# shinobi_BLE_Rev010001.net
KiCad netlist of a schematic drawn in EAGLE
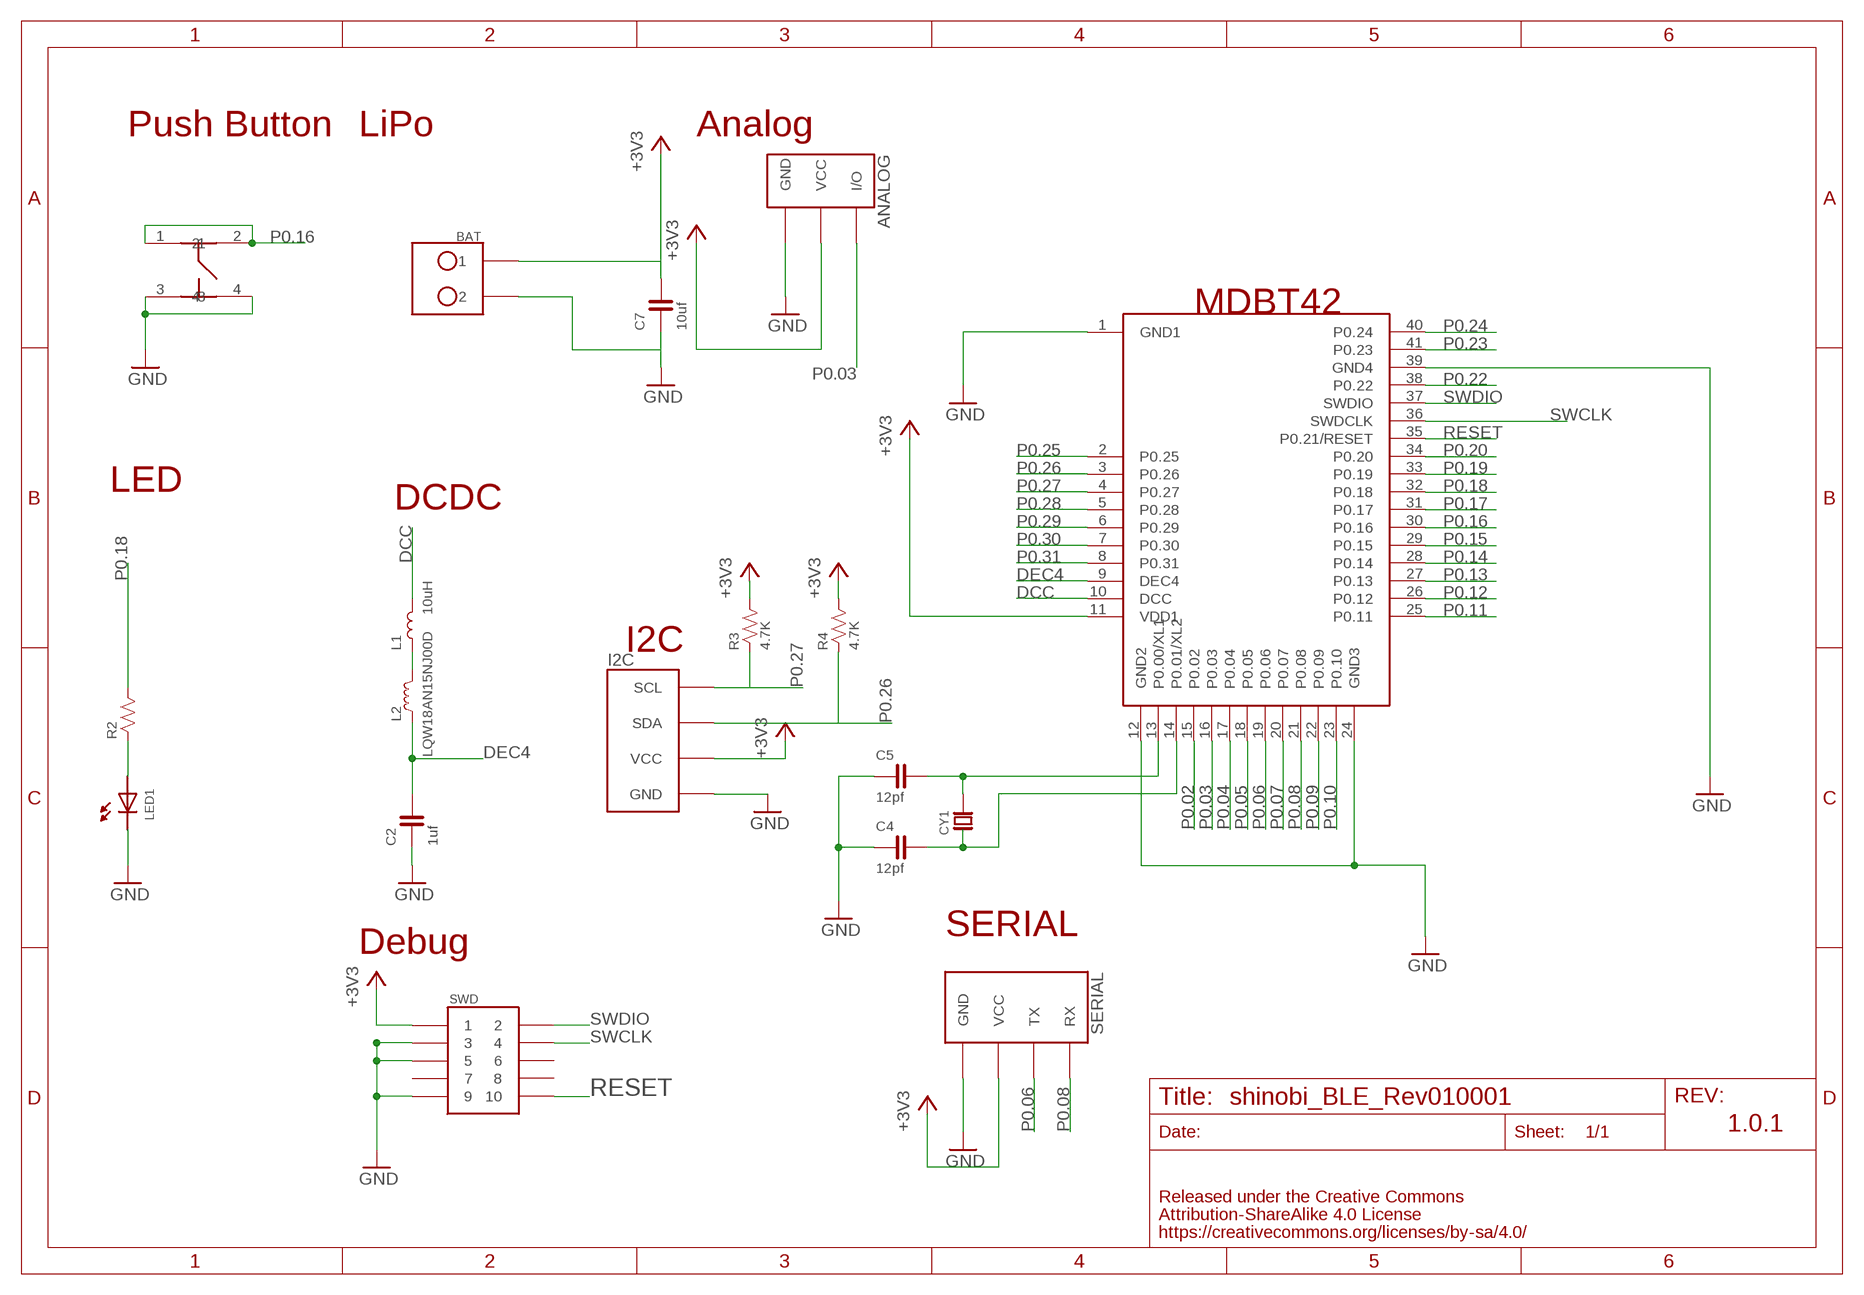
[diagram p0: schematic, sheet 1]

(export (version "E")
  (design (tool "Eeschema 10.0.6"))
  (components
    (comp (ref "ANALOG")
      (value "FABO_BRICK_3PIN-S03B-PASK-2_LONG")
      (footprint "eagle-import:FABO_BRICK_3PIN_S03B-PASK-2_LONG")
      (libsource (lib "eagle-import") (part "FABO_BRICK_3PIN-S03B-PASK-2_LONG"))
    )
    (comp (ref "BAT")
      (value "S2B-PH-SM4_TB")
      (footprint "eagle-import:S2B-PH-SM4-TB")
      (libsource (lib "eagle-import") (part "S2B-PH-SM4_TB"))
    )
    (comp (ref "C2")
      (value "1uf")
      (footprint "eagle-import:0603")
      (libsource (lib "eagle-import") (part "CAPACITOR-0603"))
    )
    (comp (ref "C4")
      (value "12pf")
      (footprint "eagle-import:0603")
      (libsource (lib "eagle-import") (part "CAPACITOR-0603"))
    )
    (comp (ref "C5")
      (value "12pf")
      (footprint "eagle-import:0603")
      (libsource (lib "eagle-import") (part "CAPACITOR-0603"))
    )
    (comp (ref "C7")
      (value "10uf")
      (footprint "eagle-import:0603")
      (libsource (lib "eagle-import") (part "CAPACITOR-0603"))
    )
    (comp (ref "CY1")
      (value "CRYSTAL-ABS07")
      (footprint "eagle-import:ABRACON-ABS07-32.768KHZ")
      (libsource (lib "eagle-import") (part "CRYSTAL-ABS07"))
    )
    (comp (ref "I2C")
      (value "FABO_BRICK_I2C-S04B-PASK-2_LONG")
      (footprint "eagle-import:FABO_BRICK_I2C_S04B-PASK-2_LONG")
      (libsource (lib "eagle-import") (part "FABO_BRICK_I2C-S04B-PASK-2_LONG"))
    )
    (comp (ref "L1")
      (value "10uH")
      (footprint "eagle-import:0603")
      (libsource (lib "eagle-import") (part "INDUCTOR-0603"))
    )
    (comp (ref "L2")
      (value "LQW18AN15NJ00D")
      (footprint "eagle-import:0603")
      (libsource (lib "eagle-import") (part "LQW18AN15NJ00D"))
    )
    (comp (ref "LED1")
      (value "LED-0603")
      (footprint "eagle-import:0603")
      (libsource (lib "eagle-import") (part "LED-0603"))
    )
    (comp (ref "R2")
      (value "RESISTOR-0603")
      (footprint "eagle-import:0603")
      (libsource (lib "eagle-import") (part "RESISTOR-0603"))
    )
    (comp (ref "R3")
      (value "4.7K")
      (footprint "eagle-import:0603")
      (libsource (lib "eagle-import") (part "RESISTOR-0603"))
    )
    (comp (ref "R4")
      (value "4.7K")
      (footprint "eagle-import:0603")
      (libsource (lib "eagle-import") (part "RESISTOR-0603"))
    )
    (comp (ref "SERIAL")
      (value "FABO_BRICK_SERIAL-S04B-PASK-2_LONG")
      (footprint "eagle-import:FABO_BRICK_SERIAL_S04B-PASK-2_LONG")
      (libsource (lib "eagle-import") (part "FABO_BRICK_SERIAL-S04B-PASK-2_LONG"))
    )
    (comp (ref "SWD")
      (value "PIN-HEADER-SMT(1.27MM)2X5")
      (footprint "eagle-import:PIN-HEADER-SMT(1.27MM)2X5")
      (libsource (lib "eagle-import") (part "PIN-HEADER-SMT(1.27MM)2X5"))
    )
    (comp (ref "U$2")
      (value "RAYTAC-MDBT42")
      (footprint "eagle-import:RAYTAC-MDBT42")
      (libsource (lib "eagle-import") (part "RAYTAC-MDBT42"))
    )
    (comp (ref "U$5")
      (value "SWICTH-4P(KMR2)")
      (footprint "eagle-import:SWITCH-4P(KMR2)")
      (libsource (lib "eagle-import") (part "SWICTH-4P(KMR2)"))
    )
  )
  (nets
    (net (code "1") (name "+3V3") (class "Default")
      (node (ref "ANALOG") (pin "VCC") (pinfunction "VCC_VCC") (pintype "bidirectional"))
      (node (ref "BAT") (pin "2") (pinfunction "1_2") (pintype "bidirectional"))
      (node (ref "C7") (pin "2") (pinfunction "2_2") (pintype "passive"))
      (node (ref "I2C") (pin "VCC") (pinfunction "VCC_VCC") (pintype "bidirectional"))
      (node (ref "R3") (pin "2") (pinfunction "2_2") (pintype "bidirectional"))
      (node (ref "R4") (pin "2") (pinfunction "2_2") (pintype "bidirectional"))
      (node (ref "SERIAL") (pin "VCC") (pinfunction "VCC_VCC") (pintype "bidirectional"))
      (node (ref "SWD") (pin "1") (pinfunction "1_1") (pintype "bidirectional"))
      (node (ref "U$2") (pin "11") (pinfunction "VDD1_11") (pintype "bidirectional"))
    )
    (net (code "2") (name "/DCC") (class "Default")
      (node (ref "L1") (pin "2") (pinfunction "2_2") (pintype "bidirectional"))
      (node (ref "U$2") (pin "10") (pinfunction "DCC_10") (pintype "bidirectional"))
    )
    (net (code "3") (name "/DEC4") (class "Default")
      (node (ref "C2") (pin "2") (pinfunction "2_2") (pintype "passive"))
      (node (ref "L2") (pin "1") (pinfunction "1_1") (pintype "bidirectional"))
      (node (ref "U$2") (pin "9") (pinfunction "DEC4_9") (pintype "bidirectional"))
    )
    (net (code "4") (name "/P0.02") (class "Default")
      (node (ref "U$2") (pin "15") (pinfunction "P0.02_15") (pintype "bidirectional"))
    )
    (net (code "5") (name "/P0.03") (class "Default")
      (node (ref "ANALOG") (pin "I/O") (pinfunction "I/O_I/O") (pintype "bidirectional"))
      (node (ref "U$2") (pin "16") (pinfunction "P0.03_16") (pintype "bidirectional"))
    )
    (net (code "6") (name "/P0.04") (class "Default")
      (node (ref "U$2") (pin "17") (pinfunction "P0.04_17") (pintype "bidirectional"))
    )
    (net (code "7") (name "/P0.05") (class "Default")
      (node (ref "U$2") (pin "18") (pinfunction "P0.05_18") (pintype "bidirectional"))
    )
    (net (code "8") (name "/P0.06") (class "Default")
      (node (ref "SERIAL") (pin "TX") (pinfunction "TX_TX") (pintype "bidirectional"))
      (node (ref "U$2") (pin "19") (pinfunction "P0.06_19") (pintype "bidirectional"))
    )
    (net (code "9") (name "/P0.07") (class "Default")
      (node (ref "U$2") (pin "20") (pinfunction "P0.07_20") (pintype "bidirectional"))
    )
    (net (code "10") (name "/P0.08") (class "Default")
      (node (ref "SERIAL") (pin "RX") (pinfunction "RX_RX") (pintype "bidirectional"))
      (node (ref "U$2") (pin "21") (pinfunction "P0.08_21") (pintype "bidirectional"))
    )
    (net (code "11") (name "/P0.09") (class "Default")
      (node (ref "U$2") (pin "22") (pinfunction "P0.09_22") (pintype "bidirectional"))
    )
    (net (code "12") (name "/P0.10") (class "Default")
      (node (ref "U$2") (pin "23") (pinfunction "P0.10_23") (pintype "bidirectional"))
    )
    (net (code "13") (name "/P0.11") (class "Default")
      (node (ref "U$2") (pin "25") (pinfunction "P0.11_25") (pintype "bidirectional"))
    )
    (net (code "14") (name "/P0.12") (class "Default")
      (node (ref "U$2") (pin "26") (pinfunction "P0.12_26") (pintype "bidirectional"))
    )
    (net (code "15") (name "/P0.13") (class "Default")
      (node (ref "U$2") (pin "27") (pinfunction "P0.13_27") (pintype "bidirectional"))
    )
    (net (code "16") (name "/P0.14") (class "Default")
      (node (ref "U$2") (pin "28") (pinfunction "P0.14_28") (pintype "bidirectional"))
    )
    (net (code "17") (name "/P0.15") (class "Default")
      (node (ref "U$2") (pin "29") (pinfunction "P0.15_29") (pintype "bidirectional"))
    )
    (net (code "18") (name "/P0.16") (class "Default")
      (node (ref "U$2") (pin "30") (pinfunction "P0.16_30") (pintype "bidirectional"))
      (node (ref "U$5") (pin "1") (pinfunction "1_1") (pintype "bidirectional"))
      (node (ref "U$5") (pin "2") (pinfunction "2_2") (pintype "bidirectional"))
    )
    (net (code "19") (name "/P0.17") (class "Default")
      (node (ref "U$2") (pin "31") (pinfunction "P0.17_31") (pintype "bidirectional"))
    )
    (net (code "20") (name "/P0.18") (class "Default")
      (node (ref "R2") (pin "2") (pinfunction "2_2") (pintype "bidirectional"))
      (node (ref "U$2") (pin "32") (pinfunction "P0.18_32") (pintype "bidirectional"))
    )
    (net (code "21") (name "/P0.19") (class "Default")
      (node (ref "U$2") (pin "33") (pinfunction "P0.19_33") (pintype "bidirectional"))
    )
    (net (code "22") (name "/P0.20") (class "Default")
      (node (ref "U$2") (pin "34") (pinfunction "P0.20_34") (pintype "bidirectional"))
    )
    (net (code "23") (name "/P0.22") (class "Default")
      (node (ref "U$2") (pin "38") (pinfunction "P0.22_38") (pintype "bidirectional"))
    )
    (net (code "24") (name "/P0.23") (class "Default")
      (node (ref "U$2") (pin "41") (pinfunction "P0.23_41") (pintype "bidirectional"))
    )
    (net (code "25") (name "/P0.24") (class "Default")
      (node (ref "U$2") (pin "40") (pinfunction "P0.24_40") (pintype "bidirectional"))
    )
    (net (code "26") (name "/P0.25") (class "Default")
      (node (ref "U$2") (pin "2") (pinfunction "P0.25_2") (pintype "bidirectional"))
    )
    (net (code "27") (name "/P0.26") (class "Default")
      (node (ref "I2C") (pin "SDA") (pinfunction "SDA_SDA") (pintype "bidirectional"))
      (node (ref "R4") (pin "1") (pinfunction "1_1") (pintype "bidirectional"))
      (node (ref "U$2") (pin "3") (pinfunction "P0.26_3") (pintype "bidirectional"))
    )
    (net (code "28") (name "/P0.27") (class "Default")
      (node (ref "I2C") (pin "SCL") (pinfunction "SCL_SCL") (pintype "bidirectional"))
      (node (ref "R3") (pin "1") (pinfunction "1_1") (pintype "bidirectional"))
      (node (ref "U$2") (pin "4") (pinfunction "P0.27_4") (pintype "bidirectional"))
    )
    (net (code "29") (name "/P0.28") (class "Default")
      (node (ref "U$2") (pin "5") (pinfunction "P0.28_5") (pintype "bidirectional"))
    )
    (net (code "30") (name "/P0.29") (class "Default")
      (node (ref "U$2") (pin "6") (pinfunction "P0.29_6") (pintype "bidirectional"))
    )
    (net (code "31") (name "/P0.30") (class "Default")
      (node (ref "U$2") (pin "7") (pinfunction "P0.30_7") (pintype "bidirectional"))
    )
    (net (code "32") (name "/P0.31") (class "Default")
      (node (ref "U$2") (pin "8") (pinfunction "P0.31_8") (pintype "bidirectional"))
    )
    (net (code "33") (name "/RESET") (class "Default")
      (node (ref "SWD") (pin "10") (pinfunction "10_10") (pintype "bidirectional"))
      (node (ref "U$2") (pin "35") (pinfunction "P0.21/RESET_35") (pintype "bidirectional"))
    )
    (net (code "34") (name "/SWCLK") (class "Default")
      (node (ref "SWD") (pin "4") (pinfunction "4_4") (pintype "bidirectional"))
      (node (ref "U$2") (pin "36") (pinfunction "SWDCLK_36") (pintype "bidirectional"))
    )
    (net (code "35") (name "/SWDIO") (class "Default")
      (node (ref "SWD") (pin "2") (pinfunction "2_2") (pintype "bidirectional"))
      (node (ref "U$2") (pin "37") (pinfunction "SWDIO_37") (pintype "bidirectional"))
    )
    (net (code "36") (name "GND") (class "Default")
      (node (ref "ANALOG") (pin "GND") (pinfunction "GND_GND") (pintype "bidirectional"))
      (node (ref "BAT") (pin "1") (pinfunction "2_1") (pintype "bidirectional"))
      (node (ref "C2") (pin "1") (pinfunction "1_1") (pintype "passive"))
      (node (ref "C4") (pin "1") (pinfunction "1_1") (pintype "passive"))
      (node (ref "C5") (pin "1") (pinfunction "1_1") (pintype "passive"))
      (node (ref "C7") (pin "1") (pinfunction "1_1") (pintype "passive"))
      (node (ref "I2C") (pin "GND") (pinfunction "GND_GND") (pintype "bidirectional"))
      (node (ref "LED1") (pin "CATHODE") (pinfunction "CATHODE_CATHODE") (pintype "passive"))
      (node (ref "SERIAL") (pin "GND") (pinfunction "GND_GND") (pintype "bidirectional"))
      (node (ref "SWD") (pin "3") (pinfunction "3_3") (pintype "bidirectional"))
      (node (ref "SWD") (pin "5") (pinfunction "5_5") (pintype "bidirectional"))
      (node (ref "SWD") (pin "9") (pinfunction "9_9") (pintype "bidirectional"))
      (node (ref "U$2") (pin "1") (pinfunction "GND1_1") (pintype "bidirectional"))
      (node (ref "U$2") (pin "12") (pinfunction "GND2_12") (pintype "bidirectional"))
      (node (ref "U$2") (pin "24") (pinfunction "GND3_24") (pintype "bidirectional"))
      (node (ref "U$2") (pin "39") (pinfunction "GND4_39") (pintype "bidirectional"))
      (node (ref "U$5") (pin "3") (pinfunction "3_3") (pintype "bidirectional"))
      (node (ref "U$5") (pin "4") (pinfunction "4_4") (pintype "bidirectional"))
    )
    (net (code "37") (name "Net-(L1-Pad1)") (class "Default")
      (node (ref "L1") (pin "1") (pinfunction "1_1") (pintype "bidirectional"))
      (node (ref "L2") (pin "2") (pinfunction "2_2") (pintype "bidirectional"))
    )
    (net (code "38") (name "Net-(LED1-PadANODE)") (class "Default")
      (node (ref "LED1") (pin "ANODE") (pinfunction "ANODE_ANODE") (pintype "passive"))
      (node (ref "R2") (pin "1") (pinfunction "1_1") (pintype "bidirectional"))
    )
    (net (code "39") (name "Net-(U$2-P0.00{slash}XL1)") (class "Default")
      (node (ref "C5") (pin "2") (pinfunction "2_2") (pintype "passive"))
      (node (ref "CY1") (pin "P$2") (pinfunction "P$2_P$2") (pintype "bidirectional"))
      (node (ref "U$2") (pin "13") (pinfunction "P0.00/XL1_13") (pintype "bidirectional"))
    )
    (net (code "40") (name "Net-(U$2-P0.01{slash}XL2)") (class "Default")
      (node (ref "C4") (pin "2") (pinfunction "2_2") (pintype "passive"))
      (node (ref "CY1") (pin "P$1") (pinfunction "P$1_P$1") (pintype "bidirectional"))
      (node (ref "U$2") (pin "14") (pinfunction "P0.01/XL2_14") (pintype "bidirectional"))
    )
    (net (code "41") (name "unconnected-(SWD-Pad6)") (class "Default")
      (node (ref "SWD") (pin "6") (pinfunction "6_6") (pintype "bidirectional"))
    )
    (net (code "42") (name "unconnected-(SWD-Pad7)") (class "Default")
      (node (ref "SWD") (pin "7") (pinfunction "7_7") (pintype "bidirectional"))
    )
    (net (code "43") (name "unconnected-(SWD-Pad8)") (class "Default")
      (node (ref "SWD") (pin "8") (pinfunction "8_8") (pintype "bidirectional"))
    )
  )
)
